# FABLAB_BADGE_01.net
KiCad netlist of a schematic drawn in Altium Designer
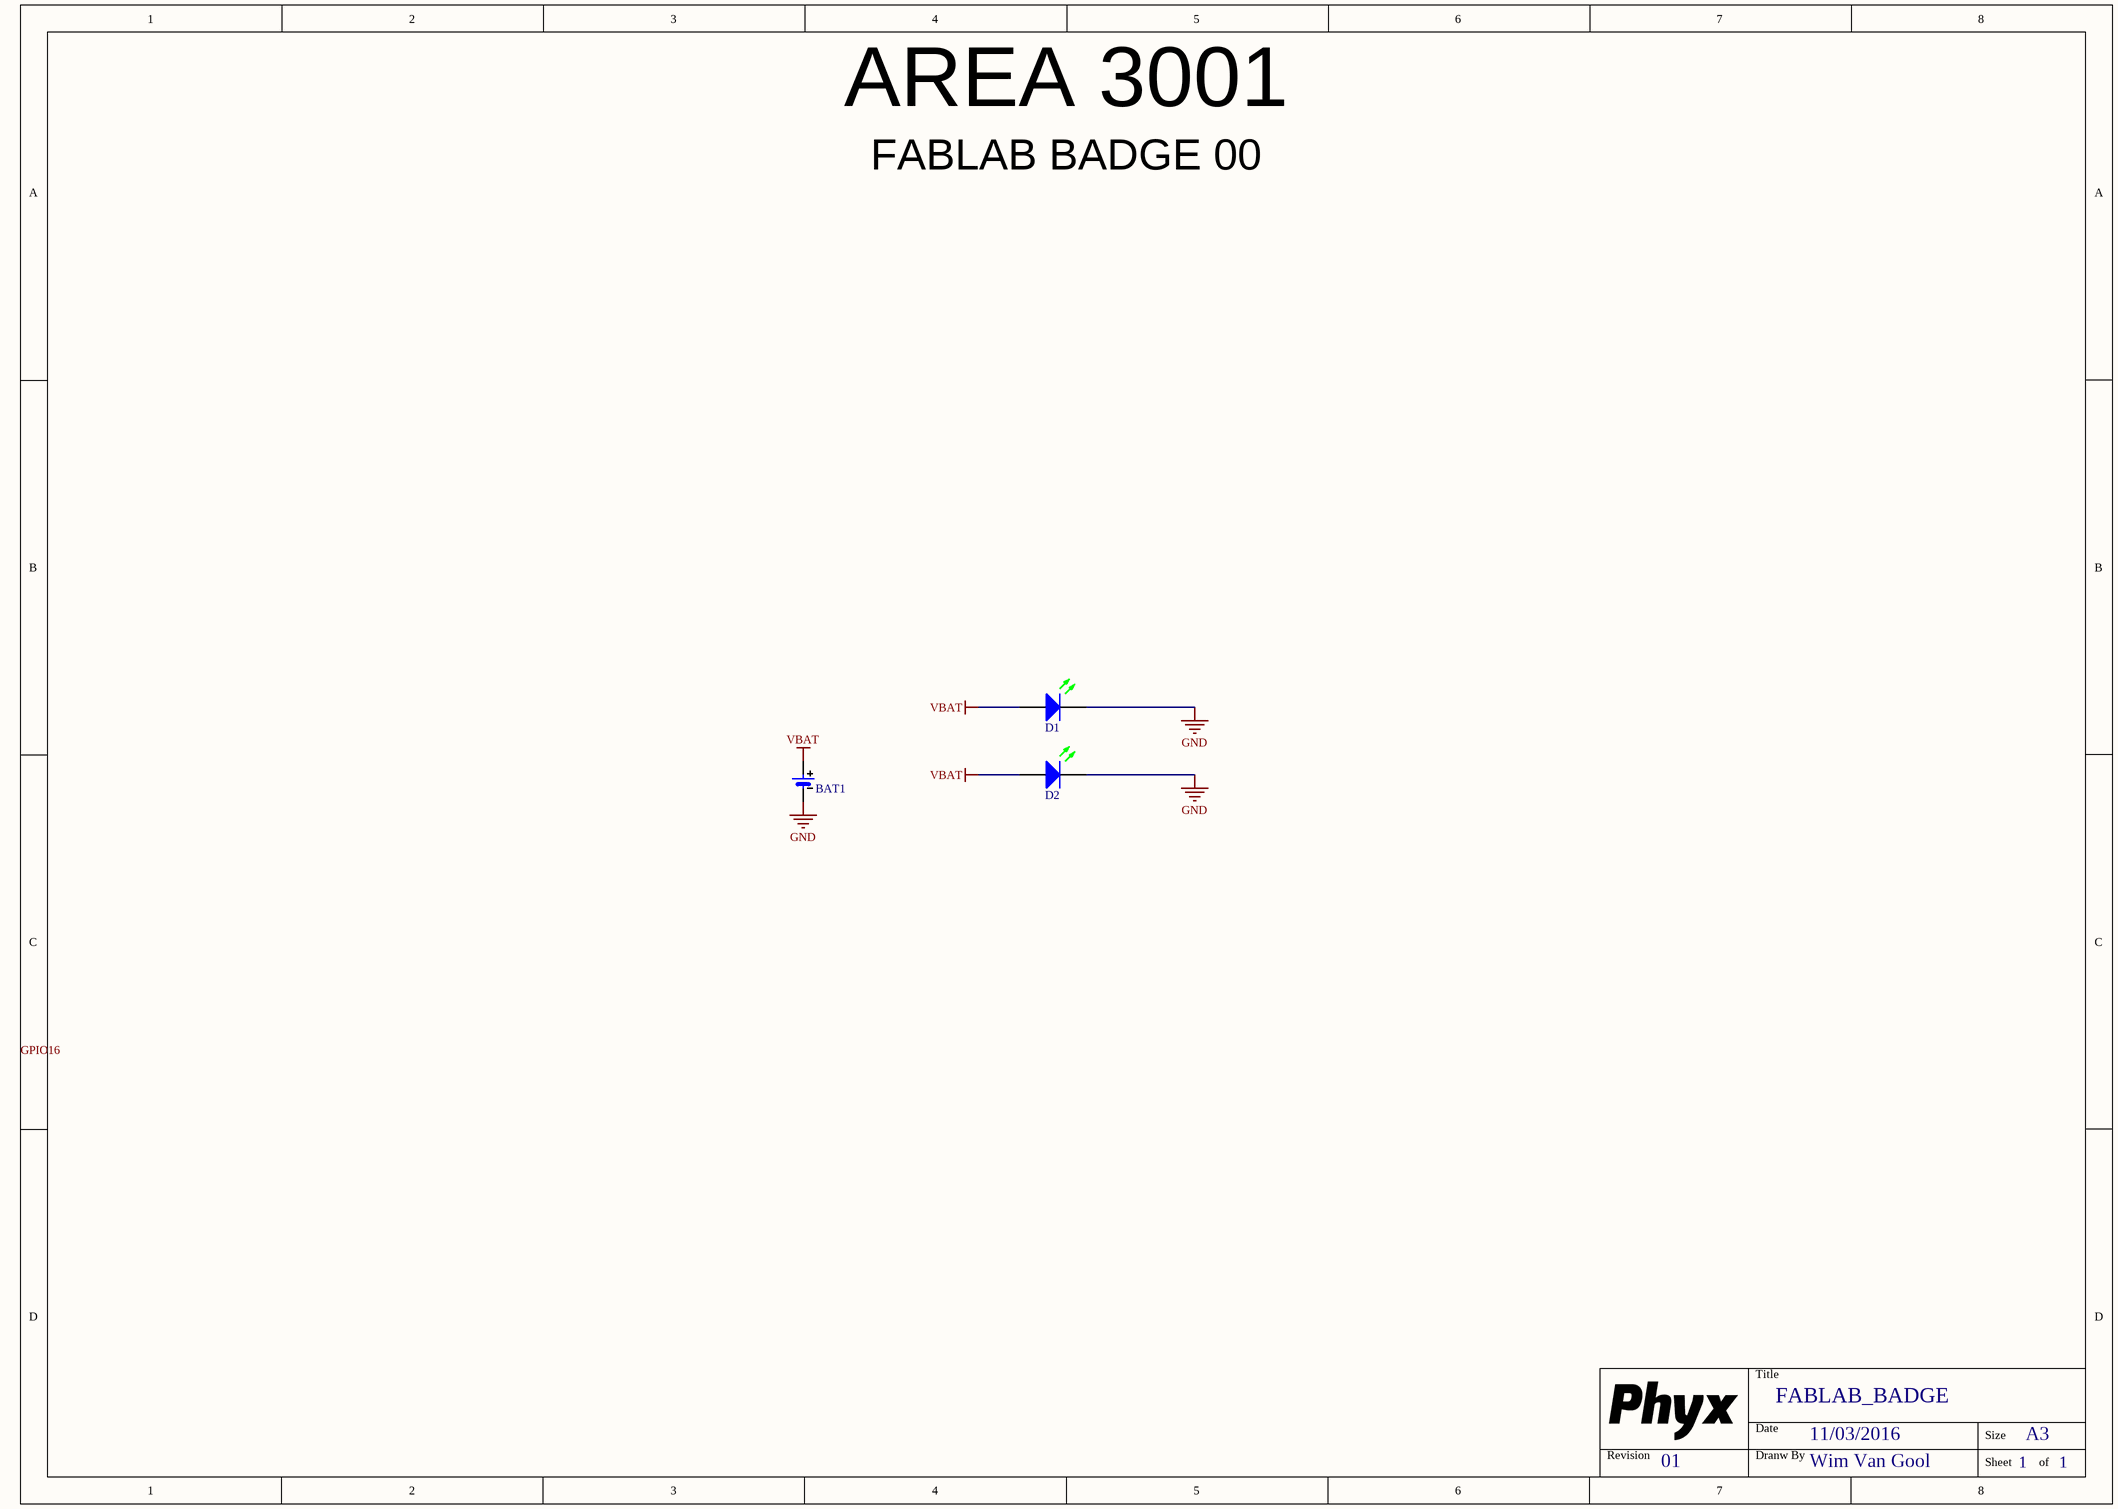
[diagram p0: FABLAB_BADGE_01.SchDoc]

(export (version "E")
  (design (tool "Eeschema 10.0.6"))
  (components
    (comp (ref "BAT1")
      (value "CR2032 Battery Holder")
      (footprint "BAT_CR2032_China")
      (description "=Description")
      (libsource (lib "Phyx_Components") (part "BAT_2"))
    )
    (comp (ref "D1")
      (value "Default 5mm Green LED")
      (footprint "LED_5MM_GR")
      (description "=Description")
      (libsource (lib "Phyx_Components") (part "LED_GREEN"))
    )
    (comp (ref "D2")
      (value "Default 5mm Green LED")
      (footprint "LED_5MM_GR")
      (description "=Description")
      (libsource (lib "Phyx_Components") (part "LED_GREEN"))
    )
  )
  (nets
    (net (code "2") (name "GND") (class "Default")
      (node (ref "BAT1") (pin "2") (pinfunction "2_2") (pintype "passive"))
      (node (ref "D1") (pin "2") (pinfunction "K_2") (pintype "passive"))
      (node (ref "D2") (pin "2") (pinfunction "K_2") (pintype "passive"))
    )
    (net (code "3") (name "VBAT") (class "Default")
      (node (ref "BAT1") (pin "1") (pinfunction "1_1") (pintype "passive"))
      (node (ref "D1") (pin "1") (pinfunction "A_1") (pintype "passive"))
      (node (ref "D2") (pin "1") (pinfunction "A_1") (pintype "passive"))
    )
  )
)
